# APP_1_FPGA_m.net
KiCad netlist of a schematic drawn in Altium Designer
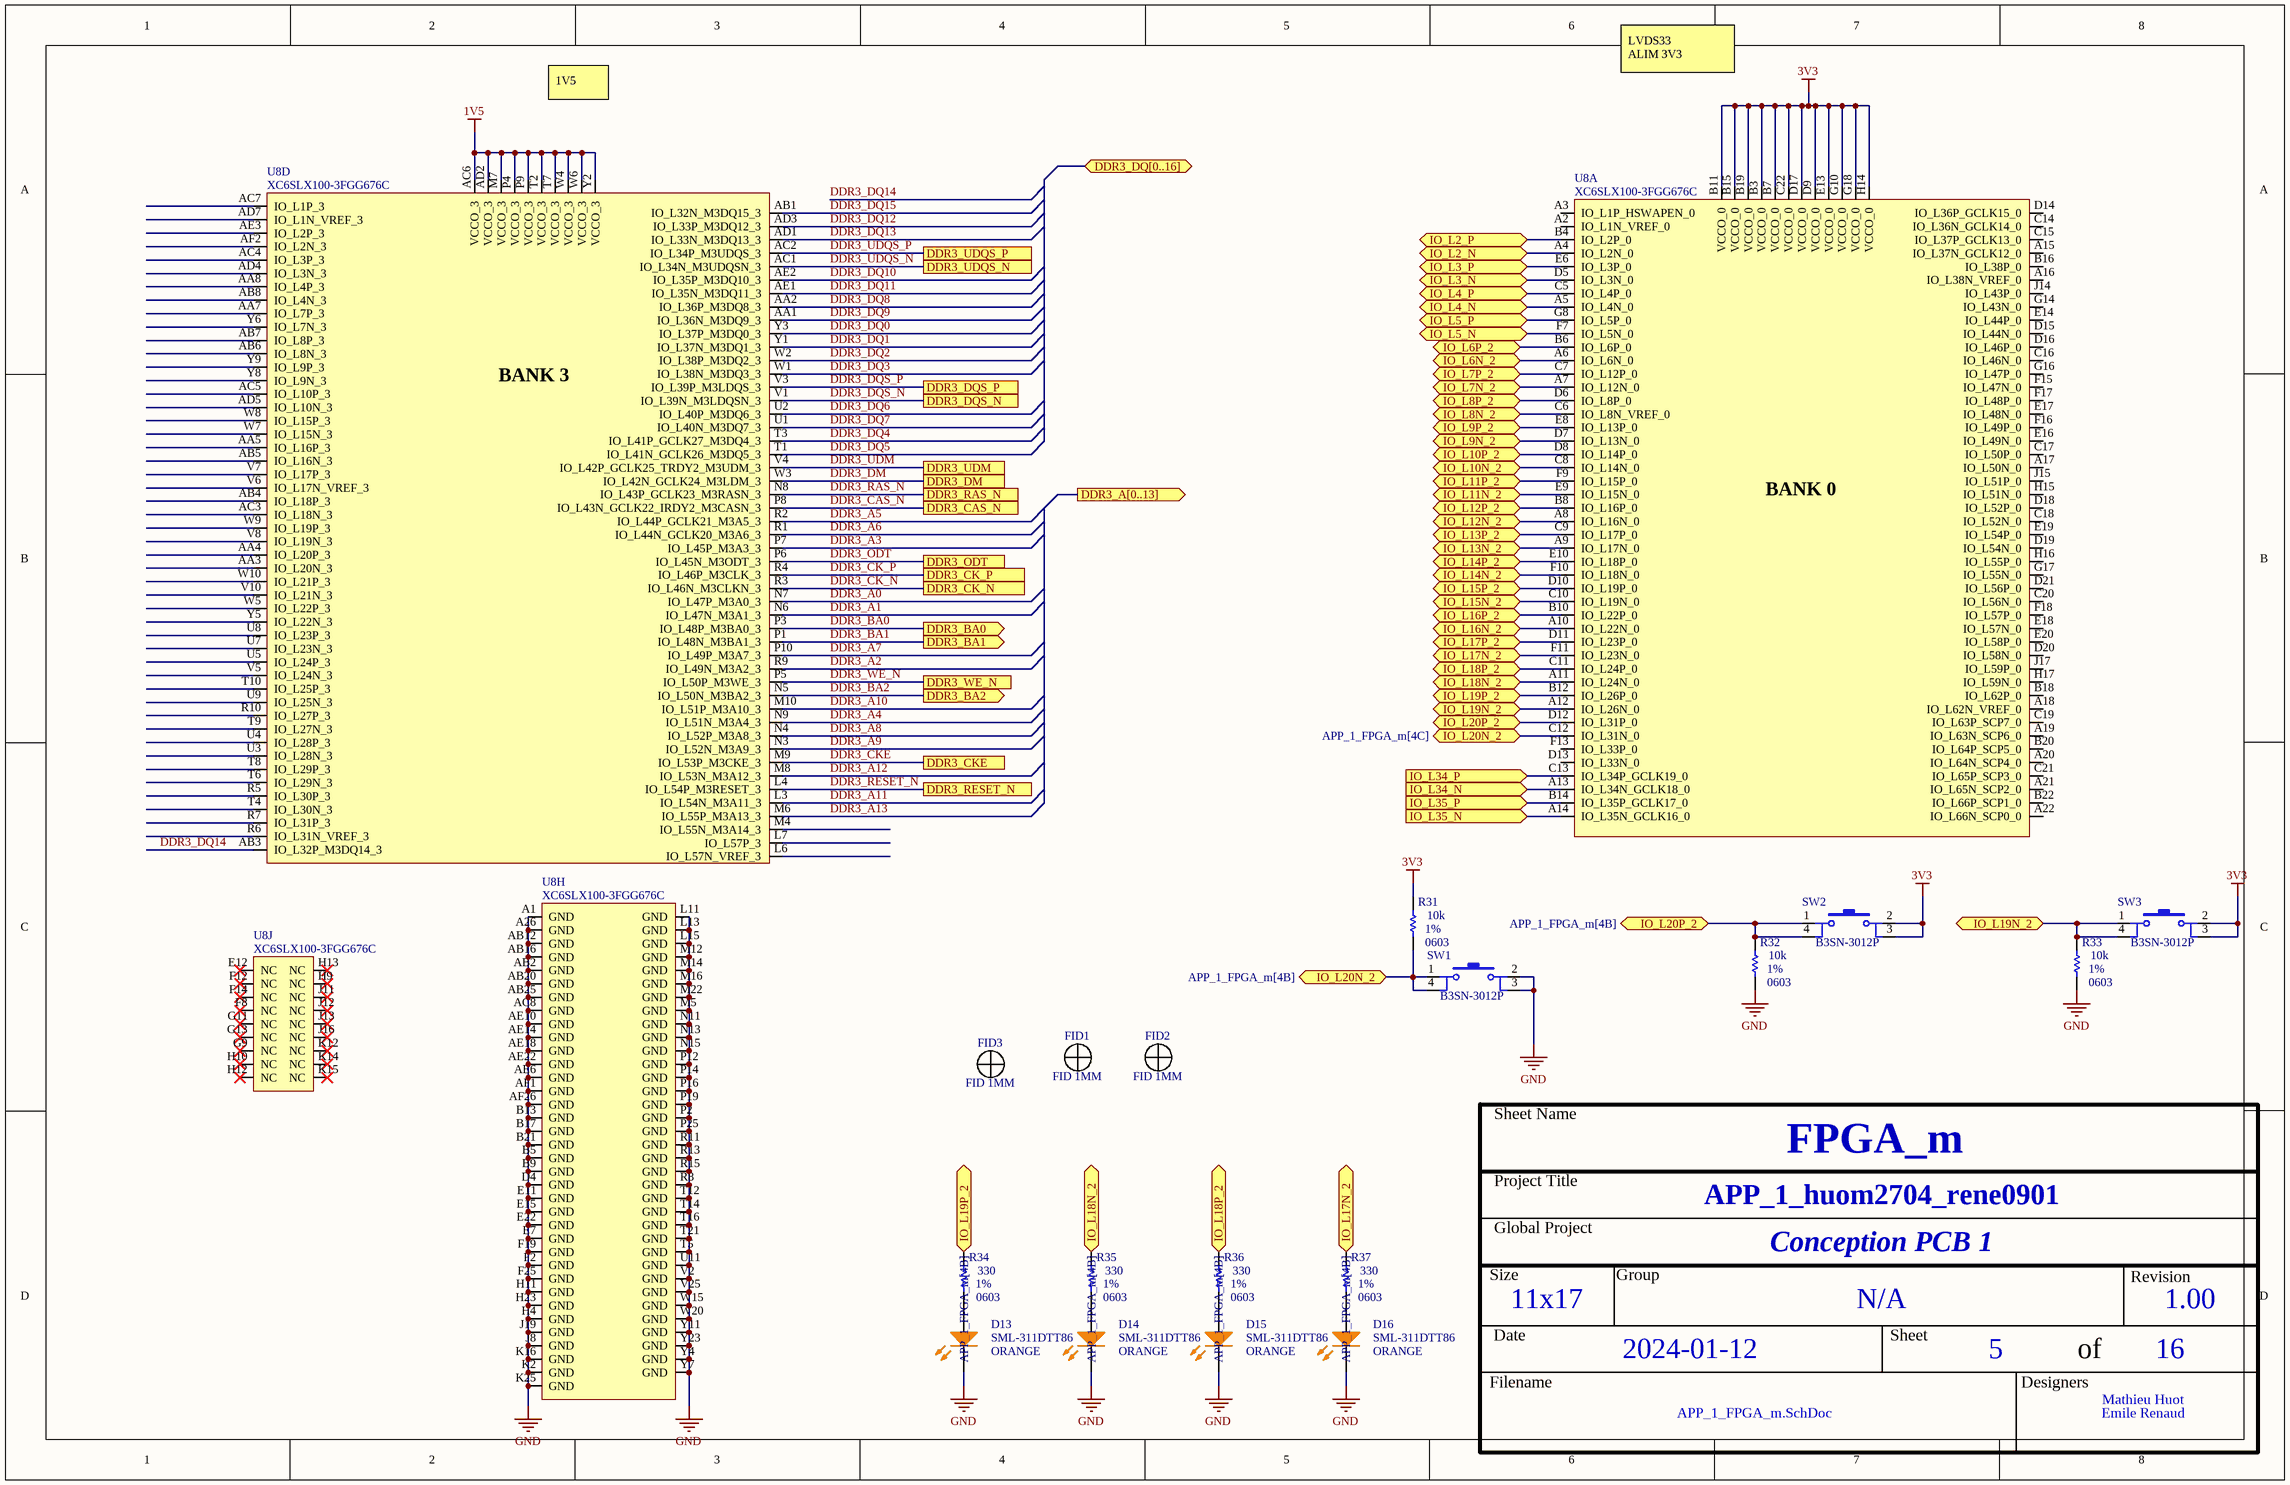
[diagram p0: APP_1_FPGA_m.SchDoc]

(export (version "E")
  (design (tool "Eeschema 10.0.6"))
  (components
    (comp (ref "D13")
      (value "SML-311DTT86")
      (footprint "LED_0603")
      (description "LED - 611nM ORANGE 2mA - 0603")
      (fields
        (field (name "VOLTAGE") "1.8V")
        (field (name "MFG") "ROHM Semiconductor")
        (field (name "ALTIUM_VALUE") "ORANGE")
        (field (name "CREATEDBY") "Jonathan Bouchard")
      )
      (libsource (lib "S7CAS_LIB2023") (part "LED_SML-311DTT86"))
    )
    (comp (ref "D14")
      (value "SML-311DTT86")
      (footprint "LED_0603")
      (description "LED - 611nM ORANGE 2mA - 0603")
      (fields
        (field (name "VOLTAGE") "1.8V")
        (field (name "MFG") "ROHM Semiconductor")
        (field (name "ALTIUM_VALUE") "ORANGE")
        (field (name "CREATEDBY") "Jonathan Bouchard")
      )
      (libsource (lib "S7CAS_LIB2023") (part "LED_SML-311DTT86"))
    )
    (comp (ref "D15")
      (value "SML-311DTT86")
      (footprint "LED_0603")
      (description "LED - 611nM ORANGE 2mA - 0603")
      (fields
        (field (name "VOLTAGE") "1.8V")
        (field (name "MFG") "ROHM Semiconductor")
        (field (name "ALTIUM_VALUE") "ORANGE")
        (field (name "CREATEDBY") "Jonathan Bouchard")
      )
      (libsource (lib "S7CAS_LIB2023") (part "LED_SML-311DTT86"))
    )
    (comp (ref "D16")
      (value "SML-311DTT86")
      (footprint "LED_0603")
      (description "LED - 611nM ORANGE 2mA - 0603")
      (fields
        (field (name "VOLTAGE") "1.8V")
        (field (name "MFG") "ROHM Semiconductor")
        (field (name "ALTIUM_VALUE") "ORANGE")
        (field (name "CREATEDBY") "Jonathan Bouchard")
      )
      (libsource (lib "S7CAS_LIB2023") (part "LED_SML-311DTT86"))
    )
    (comp (ref "FID1")
      (value "FID 1MM")
      (footprint "FID_CIRCLE_1MM")
      (description "FID - FIDUCIAL 1MM CIRCLE DOUBLE-SIDED - 1MM")
      (fields
        (field (name "CREATEDBY/DATE") "Jonathan Bouchard 2018-07-23")
        (field (name "VERIFIEDBY") "Caroline Paulin - 25 juillet 2018")
      )
      (libsource (lib "S7CAS_LIB2023") (part "FID_CIRCLE_1MM"))
    )
    (comp (ref "FID2")
      (value "FID 1MM")
      (footprint "FID_CIRCLE_1MM")
      (description "FID - FIDUCIAL 1MM CIRCLE DOUBLE-SIDED - 1MM")
      (fields
        (field (name "CREATEDBY/DATE") "Jonathan Bouchard 2018-07-23")
        (field (name "VERIFIEDBY") "Caroline Paulin - 25 juillet 2018")
      )
      (libsource (lib "S7CAS_LIB2023") (part "FID_CIRCLE_1MM"))
    )
    (comp (ref "FID3")
      (value "FID 1MM")
      (footprint "FID_CIRCLE_1MM")
      (description "FID - FIDUCIAL 1MM CIRCLE DOUBLE-SIDED - 1MM")
      (fields
        (field (name "CREATEDBY/DATE") "Jonathan Bouchard 2018-07-23")
        (field (name "VERIFIEDBY") "Caroline Paulin - 25 juillet 2018")
      )
      (libsource (lib "S7CAS_LIB2023") (part "FID_CIRCLE_1MM"))
    )
    (comp (ref "R31")
      (value "10k")
      (footprint "RES_0603")
      (description "RES - 0603")
      (fields
        (field (name "PACKAGE") "0603")
        (field (name "PRECISION") "1%")
        (field (name "CREATEDBY") "Jonathan Bouchard")
      )
      (libsource (lib "S7CAS_LIB2023") (part "RES - 0603"))
    )
    (comp (ref "R32")
      (value "10k")
      (footprint "RES_0603")
      (description "RES - 0603")
      (fields
        (field (name "PACKAGE") "0603")
        (field (name "PRECISION") "1%")
        (field (name "CREATEDBY") "Jonathan Bouchard")
      )
      (libsource (lib "S7CAS_LIB2023") (part "RES - 0603"))
    )
    (comp (ref "R33")
      (value "10k")
      (footprint "RES_0603")
      (description "RES - 0603")
      (fields
        (field (name "PACKAGE") "0603")
        (field (name "PRECISION") "1%")
        (field (name "CREATEDBY") "Jonathan Bouchard")
      )
      (libsource (lib "S7CAS_LIB2023") (part "RES - 0603"))
    )
    (comp (ref "R34")
      (value "330")
      (footprint "RES_0603")
      (description "RES - 0603")
      (fields
        (field (name "PACKAGE") "0603")
        (field (name "PRECISION") "1%")
        (field (name "CREATEDBY") "Jonathan Bouchard")
      )
      (libsource (lib "S7CAS_LIB2023") (part "RES - 0603"))
    )
    (comp (ref "R35")
      (value "330")
      (footprint "RES_0603")
      (description "RES - 0603")
      (fields
        (field (name "PACKAGE") "0603")
        (field (name "PRECISION") "1%")
        (field (name "CREATEDBY") "Jonathan Bouchard")
      )
      (libsource (lib "S7CAS_LIB2023") (part "RES - 0603"))
    )
    (comp (ref "R36")
      (value "330")
      (footprint "RES_0603")
      (description "RES - 0603")
      (fields
        (field (name "PACKAGE") "0603")
        (field (name "PRECISION") "1%")
        (field (name "CREATEDBY") "Jonathan Bouchard")
      )
      (libsource (lib "S7CAS_LIB2023") (part "RES - 0603"))
    )
    (comp (ref "R37")
      (value "330")
      (footprint "RES_0603")
      (description "RES - 0603")
      (fields
        (field (name "PACKAGE") "0603")
        (field (name "PRECISION") "1%")
        (field (name "CREATEDBY") "Jonathan Bouchard")
      )
      (libsource (lib "S7CAS_LIB2023") (part "RES - 0603"))
    )
    (comp (ref "SW1")
      (value "B3SN-3012P")
      (footprint "SWI_TACT_B3SN-3012P")
      (description "SWI - TACT SPST-NO 0.05A 24V - 4-SMD")
      (fields
        (field (name "MFG") "Omron")
        (field (name "VOLTAGE") "24V")
        (field (name "CREATEDBY") "Jonathan Bouchard")
      )
      (libsource (lib "S7CAS_LIB2023") (part "SWI_TACT_B3SN-3012P"))
    )
    (comp (ref "SW2")
      (value "B3SN-3012P")
      (footprint "SWI_TACT_B3SN-3012P")
      (description "SWI - TACT SPST-NO 0.05A 24V - 4-SMD")
      (fields
        (field (name "MFG") "Omron")
        (field (name "VOLTAGE") "24V")
        (field (name "CREATEDBY") "Jonathan Bouchard")
      )
      (libsource (lib "S7CAS_LIB2023") (part "SWI_TACT_B3SN-3012P"))
    )
    (comp (ref "SW3")
      (value "B3SN-3012P")
      (footprint "SWI_TACT_B3SN-3012P")
      (description "SWI - TACT SPST-NO 0.05A 24V - 4-SMD")
      (fields
        (field (name "MFG") "Omron")
        (field (name "VOLTAGE") "24V")
        (field (name "CREATEDBY") "Jonathan Bouchard")
      )
      (libsource (lib "S7CAS_LIB2023") (part "SWI_TACT_B3SN-3012P"))
    )
    (comp (ref "U8")
      (value "XC6SLX100-3FGG676C")
      (footprint "FPGA_XILINX_FGG676")
      (description "FPGA - XILINX SPARTAN 6 480 I/O - BGA-676")
      (fields
        (field (name "VOLTAGE") "1.14 V ~ 1.26 V")
        (field (name "MFG") "Xilinx")
        (field (name "CREATEDBY") "Jonathan Bouchard")
      )
      (libsource (lib "S7CAS_LIB2023") (part "FPGA_XC6SLX100-3FGG676C"))
    )
  )
  (nets
    (net (code "2") (name "/DDR3_A0") (class "Default")
      (node (ref "U8") (pin "N7") (pinfunction "IO_L47P_M3A0_3_N7") (pintype "passive"))
    )
    (net (code "3") (name "/DDR3_A1") (class "Default")
      (node (ref "U8") (pin "N6") (pinfunction "IO_L47N_M3A1_3_N6") (pintype "passive"))
    )
    (net (code "4") (name "/DDR3_A2") (class "Default")
      (node (ref "U8") (pin "R9") (pinfunction "IO_L49N_M3A2_3_R9") (pintype "passive"))
    )
    (net (code "5") (name "/DDR3_A3") (class "Default")
      (node (ref "U8") (pin "P7") (pinfunction "IO_L45P_M3A3_3_P7") (pintype "passive"))
    )
    (net (code "6") (name "/DDR3_A4") (class "Default")
      (node (ref "U8") (pin "N9") (pinfunction "IO_L51N_M3A4_3_N9") (pintype "passive"))
    )
    (net (code "7") (name "/DDR3_A5") (class "Default")
      (node (ref "U8") (pin "R2") (pinfunction "IO_L44P_GCLK21_M3A5_3_R2") (pintype "passive"))
    )
    (net (code "8") (name "/DDR3_A6") (class "Default")
      (node (ref "U8") (pin "R1") (pinfunction "IO_L44N_GCLK20_M3A6_3_R1") (pintype "passive"))
    )
    (net (code "9") (name "/DDR3_A7") (class "Default")
      (node (ref "U8") (pin "P10") (pinfunction "IO_L49P_M3A7_3_P10") (pintype "passive"))
    )
    (net (code "10") (name "/DDR3_A8") (class "Default")
      (node (ref "U8") (pin "N4") (pinfunction "IO_L52P_M3A8_3_N4") (pintype "passive"))
    )
    (net (code "11") (name "/DDR3_A9") (class "Default")
      (node (ref "U8") (pin "N3") (pinfunction "IO_L52N_M3A9_3_N3") (pintype "passive"))
    )
    (net (code "12") (name "/DDR3_A10") (class "Default")
      (node (ref "U8") (pin "M10") (pinfunction "IO_L51P_M3A10_3_M10") (pintype "passive"))
    )
    (net (code "13") (name "/DDR3_A11") (class "Default")
      (node (ref "U8") (pin "L3") (pinfunction "IO_L54N_M3A11_3_L3") (pintype "passive"))
    )
    (net (code "14") (name "/DDR3_A12") (class "Default")
      (node (ref "U8") (pin "M8") (pinfunction "IO_L53N_M3A12_3_M8") (pintype "passive"))
    )
    (net (code "15") (name "/DDR3_A13") (class "Default")
      (node (ref "U8") (pin "M6") (pinfunction "IO_L55P_M3A13_3_M6") (pintype "passive"))
    )
    (net (code "17") (name "/DDR3_BA0") (class "Default")
      (node (ref "U8") (pin "P3") (pinfunction "IO_L48P_M3BA0_3_P3") (pintype "passive"))
    )
    (net (code "18") (name "/DDR3_BA1") (class "Default")
      (node (ref "U8") (pin "P1") (pinfunction "IO_L48N_M3BA1_3_P1") (pintype "passive"))
    )
    (net (code "19") (name "/DDR3_BA2") (class "Default")
      (node (ref "U8") (pin "N5") (pinfunction "IO_L50N_M3BA2_3_N5") (pintype "passive"))
    )
    (net (code "20") (name "/DDR3_CAS_N") (class "Default")
      (node (ref "U8") (pin "P8") (pinfunction "IO_L43N_GCLK22_IRDY2_M3CASN_3_P8") (pintype "passive"))
    )
    (net (code "21") (name "/DDR3_CKE") (class "Default")
      (node (ref "U8") (pin "M9") (pinfunction "IO_L53P_M3CKE_3_M9") (pintype "passive"))
    )
    (net (code "22") (name "/DDR3_CK_N") (class "Default")
      (node (ref "U8") (pin "R3") (pinfunction "IO_L46N_M3CLKN_3_R3") (pintype "passive"))
    )
    (net (code "23") (name "/DDR3_CK_P") (class "Default")
      (node (ref "U8") (pin "R4") (pinfunction "IO_L46P_M3CLK_3_R4") (pintype "passive"))
    )
    (net (code "24") (name "/DDR3_DM") (class "Default")
      (node (ref "U8") (pin "W3") (pinfunction "IO_L42N_GCLK24_M3LDM_3_W3") (pintype "passive"))
    )
    (net (code "25") (name "/DDR3_DQ0") (class "Default")
      (node (ref "U8") (pin "Y3") (pinfunction "IO_L37P_M3DQ0_3_Y3") (pintype "passive"))
    )
    (net (code "26") (name "/DDR3_DQ1") (class "Default")
      (node (ref "U8") (pin "Y1") (pinfunction "IO_L37N_M3DQ1_3_Y1") (pintype "passive"))
    )
    (net (code "27") (name "/DDR3_DQ2") (class "Default")
      (node (ref "U8") (pin "W2") (pinfunction "IO_L38P_M3DQ2_3_W2") (pintype "passive"))
    )
    (net (code "28") (name "/DDR3_DQ3") (class "Default")
      (node (ref "U8") (pin "W1") (pinfunction "IO_L38N_M3DQ3_3_W1") (pintype "passive"))
    )
    (net (code "29") (name "/DDR3_DQ4") (class "Default")
      (node (ref "U8") (pin "T3") (pinfunction "IO_L41P_GCLK27_M3DQ4_3_T3") (pintype "passive"))
    )
    (net (code "30") (name "/DDR3_DQ5") (class "Default")
      (node (ref "U8") (pin "T1") (pinfunction "IO_L41N_GCLK26_M3DQ5_3_T1") (pintype "passive"))
    )
    (net (code "31") (name "/DDR3_DQ6") (class "Default")
      (node (ref "U8") (pin "U2") (pinfunction "IO_L40P_M3DQ6_3_U2") (pintype "passive"))
    )
    (net (code "32") (name "/DDR3_DQ7") (class "Default")
      (node (ref "U8") (pin "U1") (pinfunction "IO_L40N_M3DQ7_3_U1") (pintype "passive"))
    )
    (net (code "33") (name "/DDR3_DQ8") (class "Default")
      (node (ref "U8") (pin "AA2") (pinfunction "IO_L36P_M3DQ8_3_AA2") (pintype "passive"))
    )
    (net (code "34") (name "/DDR3_DQ9") (class "Default")
      (node (ref "U8") (pin "AA1") (pinfunction "IO_L36N_M3DQ9_3_AA1") (pintype "passive"))
    )
    (net (code "35") (name "/DDR3_DQ10") (class "Default")
      (node (ref "U8") (pin "AE2") (pinfunction "IO_L35P_M3DQ10_3_AE2") (pintype "passive"))
    )
    (net (code "36") (name "/DDR3_DQ11") (class "Default")
      (node (ref "U8") (pin "AE1") (pinfunction "IO_L35N_M3DQ11_3_AE1") (pintype "passive"))
    )
    (net (code "37") (name "/DDR3_DQ12") (class "Default")
      (node (ref "U8") (pin "AD3") (pinfunction "IO_L33P_M3DQ12_3_AD3") (pintype "passive"))
    )
    (net (code "38") (name "/DDR3_DQ13") (class "Default")
      (node (ref "U8") (pin "AD1") (pinfunction "IO_L33N_M3DQ13_3_AD1") (pintype "passive"))
    )
    (net (code "39") (name "/DDR3_DQ14") (class "Default")
      (node (ref "U8") (pin "AB3") (pinfunction "IO_L32P_M3DQ14_3_AB3") (pintype "passive"))
    )
    (net (code "40") (name "/DDR3_DQ15") (class "Default")
      (node (ref "U8") (pin "AB1") (pinfunction "IO_L32N_M3DQ15_3_AB1") (pintype "passive"))
    )
    (net (code "41") (name "/DDR3_DQS_N") (class "Default")
      (node (ref "U8") (pin "V1") (pinfunction "IO_L39N_M3LDQSN_3_V1") (pintype "passive"))
    )
    (net (code "42") (name "/DDR3_DQS_P") (class "Default")
      (node (ref "U8") (pin "V3") (pinfunction "IO_L39P_M3LDQS_3_V3") (pintype "passive"))
    )
    (net (code "44") (name "/DDR3_ODT") (class "Default")
      (node (ref "U8") (pin "P6") (pinfunction "IO_L45N_M3ODT_3_P6") (pintype "passive"))
    )
    (net (code "45") (name "/DDR3_RAS_N") (class "Default")
      (node (ref "U8") (pin "N8") (pinfunction "IO_L43P_GCLK23_M3RASN_3_N8") (pintype "passive"))
    )
    (net (code "46") (name "/DDR3_RESET_N") (class "Default")
      (node (ref "U8") (pin "L4") (pinfunction "IO_L54P_M3RESET_3_L4") (pintype "passive"))
    )
    (net (code "47") (name "/DDR3_UDM") (class "Default")
      (node (ref "U8") (pin "V4") (pinfunction "IO_L42P_GCLK25_TRDY2_M3UDM_3_V4") (pintype "passive"))
    )
    (net (code "48") (name "/DDR3_UDQS_N") (class "Default")
      (node (ref "U8") (pin "AC1") (pinfunction "IO_L34N_M3UDQSN_3_AC1") (pintype "passive"))
    )
    (net (code "49") (name "/DDR3_UDQS_P") (class "Default")
      (node (ref "U8") (pin "AC2") (pinfunction "IO_L34P_M3UDQS_3_AC2") (pintype "passive"))
    )
    (net (code "50") (name "/DDR3_WE_N") (class "Default")
      (node (ref "U8") (pin "P5") (pinfunction "IO_L50P_M3WE_3_P5") (pintype "passive"))
    )
    (net (code "51") (name "/IO_L2_N") (class "Default")
      (node (ref "U8") (pin "A4") (pinfunction "IO_L2N_0_A4") (pintype "passive"))
    )
    (net (code "52") (name "/IO_L2_P") (class "Default")
      (node (ref "U8") (pin "B4") (pinfunction "IO_L2P_0_B4") (pintype "passive"))
    )
    (net (code "53") (name "/IO_L3_N") (class "Default")
      (node (ref "U8") (pin "D5") (pinfunction "IO_L3N_0_D5") (pintype "passive"))
    )
    (net (code "54") (name "/IO_L3_P") (class "Default")
      (node (ref "U8") (pin "E6") (pinfunction "IO_L3P_0_E6") (pintype "passive"))
    )
    (net (code "55") (name "/IO_L4_N") (class "Default")
      (node (ref "U8") (pin "A5") (pinfunction "IO_L4N_0_A5") (pintype "passive"))
    )
    (net (code "56") (name "/IO_L4_P") (class "Default")
      (node (ref "U8") (pin "C5") (pinfunction "IO_L4P_0_C5") (pintype "passive"))
    )
    (net (code "57") (name "/IO_L5_N") (class "Default")
      (node (ref "U8") (pin "F7") (pinfunction "IO_L5N_0_F7") (pintype "passive"))
    )
    (net (code "58") (name "/IO_L5_P") (class "Default")
      (node (ref "U8") (pin "G8") (pinfunction "IO_L5P_0_G8") (pintype "passive"))
    )
    (net (code "59") (name "/IO_L6N_2") (class "Default")
      (node (ref "U8") (pin "A6") (pinfunction "IO_L6N_0_A6") (pintype "passive"))
    )
    (net (code "60") (name "/IO_L6P_2") (class "Default")
      (node (ref "U8") (pin "B6") (pinfunction "IO_L6P_0_B6") (pintype "passive"))
    )
    (net (code "61") (name "/IO_L7N_2") (class "Default")
      (node (ref "U8") (pin "A7") (pinfunction "IO_L12N_0_A7") (pintype "passive"))
    )
    (net (code "62") (name "/IO_L7P_2") (class "Default")
      (node (ref "U8") (pin "C7") (pinfunction "IO_L12P_0_C7") (pintype "passive"))
    )
    (net (code "63") (name "/IO_L8N_2") (class "Default")
      (node (ref "U8") (pin "C6") (pinfunction "IO_L8N_VREF_0_C6") (pintype "passive"))
    )
    (net (code "64") (name "/IO_L8P_2") (class "Default")
      (node (ref "U8") (pin "D6") (pinfunction "IO_L8P_0_D6") (pintype "passive"))
    )
    (net (code "65") (name "/IO_L9N_2") (class "Default")
      (node (ref "U8") (pin "D7") (pinfunction "IO_L13N_0_D7") (pintype "passive"))
    )
    (net (code "66") (name "/IO_L9P_2") (class "Default")
      (node (ref "U8") (pin "E8") (pinfunction "IO_L13P_0_E8") (pintype "passive"))
    )
    (net (code "67") (name "/IO_L10N_2") (class "Default")
      (node (ref "U8") (pin "C8") (pinfunction "IO_L14N_0_C8") (pintype "passive"))
    )
    (net (code "68") (name "/IO_L10P_2") (class "Default")
      (node (ref "U8") (pin "D8") (pinfunction "IO_L14P_0_D8") (pintype "passive"))
    )
    (net (code "69") (name "/IO_L11N_2") (class "Default")
      (node (ref "U8") (pin "E9") (pinfunction "IO_L15N_0_E9") (pintype "passive"))
    )
    (net (code "70") (name "/IO_L11P_2") (class "Default")
      (node (ref "U8") (pin "F9") (pinfunction "IO_L15P_0_F9") (pintype "passive"))
    )
    (net (code "71") (name "/IO_L12N_2") (class "Default")
      (node (ref "U8") (pin "A8") (pinfunction "IO_L16N_0_A8") (pintype "passive"))
    )
    (net (code "72") (name "/IO_L12P_2") (class "Default")
      (node (ref "U8") (pin "B8") (pinfunction "IO_L16P_0_B8") (pintype "passive"))
    )
    (net (code "73") (name "/IO_L13N_2") (class "Default")
      (node (ref "U8") (pin "A9") (pinfunction "IO_L17N_0_A9") (pintype "passive"))
    )
    (net (code "74") (name "/IO_L13P_2") (class "Default")
      (node (ref "U8") (pin "C9") (pinfunction "IO_L17P_0_C9") (pintype "passive"))
    )
    (net (code "75") (name "/IO_L14N_2") (class "Default")
      (node (ref "U8") (pin "F10") (pinfunction "IO_L18N_0_F10") (pintype "passive"))
    )
    (net (code "76") (name "/IO_L14P_2") (class "Default")
      (node (ref "U8") (pin "E10") (pinfunction "IO_L18P_0_E10") (pintype "passive"))
    )
    (net (code "77") (name "/IO_L15N_2") (class "Default")
      (node (ref "U8") (pin "C10") (pinfunction "IO_L19N_0_C10") (pintype "passive"))
    )
    (net (code "78") (name "/IO_L15P_2") (class "Default")
      (node (ref "U8") (pin "D10") (pinfunction "IO_L19P_0_D10") (pintype "passive"))
    )
    (net (code "79") (name "/IO_L16N_2") (class "Default")
      (node (ref "U8") (pin "A10") (pinfunction "IO_L22N_0_A10") (pintype "passive"))
    )
    (net (code "80") (name "/IO_L16P_2") (class "Default")
      (node (ref "U8") (pin "B10") (pinfunction "IO_L22P_0_B10") (pintype "passive"))
    )
    (net (code "81") (name "/IO_L17N_2") (class "Default")
      (node (ref "R37") (pin "2") (pinfunction "2_2") (pintype "passive"))
      (node (ref "U8") (pin "F11") (pinfunction "IO_L23N_0_F11") (pintype "passive"))
    )
    (net (code "82") (name "/IO_L17P_2") (class "Default")
      (node (ref "U8") (pin "D11") (pinfunction "IO_L23P_0_D11") (pintype "passive"))
    )
    (net (code "83") (name "/IO_L18N_2") (class "Default")
      (node (ref "R35") (pin "2") (pinfunction "2_2") (pintype "passive"))
      (node (ref "U8") (pin "A11") (pinfunction "IO_L24N_0_A11") (pintype "passive"))
    )
    (net (code "84") (name "/IO_L18P_2") (class "Default")
      (node (ref "R36") (pin "2") (pinfunction "2_2") (pintype "passive"))
      (node (ref "U8") (pin "C11") (pinfunction "IO_L24P_0_C11") (pintype "passive"))
    )
    (net (code "85") (name "/IO_L19N_2") (class "Default")
      (node (ref "R33") (pin "2") (pinfunction "2_2") (pintype "passive"))
      (node (ref "SW3") (pin "1") (pinfunction "1_1") (pintype "passive"))
      (node (ref "SW3") (pin "4") (pinfunction "4_4") (pintype "passive"))
      (node (ref "U8") (pin "A12") (pinfunction "IO_L26N_0_A12") (pintype "passive"))
    )
    (net (code "86") (name "/IO_L19P_2") (class "Default")
      (node (ref "R34") (pin "2") (pinfunction "2_2") (pintype "passive"))
      (node (ref "U8") (pin "B12") (pinfunction "IO_L26P_0_B12") (pintype "passive"))
    )
    (net (code "87") (name "/IO_L20N_2") (class "Default")
      (node (ref "R31") (pin "1") (pinfunction "1_1") (pintype "passive"))
      (node (ref "SW1") (pin "1") (pinfunction "1_1") (pintype "passive"))
      (node (ref "SW1") (pin "4") (pinfunction "4_4") (pintype "passive"))
      (node (ref "U8") (pin "C12") (pinfunction "IO_L31N_0_C12") (pintype "passive"))
    )
    (net (code "88") (name "/IO_L20P_2") (class "Default")
      (node (ref "R32") (pin "2") (pinfunction "2_2") (pintype "passive"))
      (node (ref "SW2") (pin "1") (pinfunction "1_1") (pintype "passive"))
      (node (ref "SW2") (pin "4") (pinfunction "4_4") (pintype "passive"))
      (node (ref "U8") (pin "D12") (pinfunction "IO_L31P_0_D12") (pintype "passive"))
    )
    (net (code "89") (name "/IO_L34_N") (class "Default")
      (node (ref "U8") (pin "A13") (pinfunction "IO_L34N_GCLK18_0_A13") (pintype "passive"))
    )
    (net (code "90") (name "/IO_L34_P") (class "Default")
      (node (ref "U8") (pin "C13") (pinfunction "IO_L34P_GCLK19_0_C13") (pintype "passive"))
    )
    (net (code "91") (name "/IO_L35_N") (class "Default")
      (node (ref "U8") (pin "A14") (pinfunction "IO_L35N_GCLK16_0_A14") (pintype "passive"))
    )
    (net (code "92") (name "/IO_L35_P") (class "Default")
      (node (ref "U8") (pin "B14") (pinfunction "IO_L35P_GCLK17_0_B14") (pintype "passive"))
    )
    (net (code "93") (name "1V5") (class "Default")
      (node (ref "U8") (pin "AC6") (pinfunction "VCCO_3_AC6") (pintype "passive"))
      (node (ref "U8") (pin "AD2") (pinfunction "VCCO_3_AD2") (pintype "passive"))
      (node (ref "U8") (pin "M7") (pinfunction "VCCO_3_M7") (pintype "passive"))
      (node (ref "U8") (pin "P4") (pinfunction "VCCO_3_P4") (pintype "passive"))
      (node (ref "U8") (pin "P9") (pinfunction "VCCO_3_P9") (pintype "passive"))
      (node (ref "U8") (pin "T2") (pinfunction "VCCO_3_T2") (pintype "passive"))
      (node (ref "U8") (pin "T7") (pinfunction "VCCO_3_T7") (pintype "passive"))
      (node (ref "U8") (pin "W4") (pinfunction "VCCO_3_W4") (pintype "passive"))
      (node (ref "U8") (pin "W6") (pinfunction "VCCO_3_W6") (pintype "passive"))
      (node (ref "U8") (pin "Y2") (pinfunction "VCCO_3_Y2") (pintype "passive"))
    )
    (net (code "94") (name "3V3") (class "Default")
      (node (ref "R31") (pin "2") (pinfunction "2_2") (pintype "passive"))
      (node (ref "SW2") (pin "2") (pinfunction "2_2") (pintype "passive"))
      (node (ref "SW2") (pin "3") (pinfunction "3_3") (pintype "passive"))
      (node (ref "SW3") (pin "2") (pinfunction "2_2") (pintype "passive"))
      (node (ref "SW3") (pin "3") (pinfunction "3_3") (pintype "passive"))
      (node (ref "U8") (pin "B11") (pinfunction "VCCO_0_B11") (pintype "passive"))
      (node (ref "U8") (pin "B15") (pinfunction "VCCO_0_B15") (pintype "passive"))
      (node (ref "U8") (pin "B19") (pinfunction "VCCO_0_B19") (pintype "passive"))
      (node (ref "U8") (pin "B3") (pinfunction "VCCO_0_B3") (pintype "passive"))
      (node (ref "U8") (pin "B7") (pinfunction "VCCO_0_B7") (pintype "passive"))
      (node (ref "U8") (pin "C22") (pinfunction "VCCO_0_C22") (pintype "passive"))
      (node (ref "U8") (pin "D17") (pinfunction "VCCO_0_D17") (pintype "passive"))
      (node (ref "U8") (pin "D9") (pinfunction "VCCO_0_D9") (pintype "passive"))
      (node (ref "U8") (pin "E13") (pinfunction "VCCO_0_E13") (pintype "passive"))
      (node (ref "U8") (pin "G10") (pinfunction "VCCO_0_G10") (pintype "passive"))
      (node (ref "U8") (pin "G18") (pinfunction "VCCO_0_G18") (pintype "passive"))
      (node (ref "U8") (pin "H14") (pinfunction "VCCO_0_H14") (pintype "passive"))
    )
    (net (code "95") (name "GND") (class "Default")
      (node (ref "D13") (pin "K") (pinfunction "K_K") (pintype "passive"))
      (node (ref "D14") (pin "K") (pinfunction "K_K") (pintype "passive"))
      (node (ref "D15") (pin "K") (pinfunction "K_K") (pintype "passive"))
      (node (ref "D16") (pin "K") (pinfunction "K_K") (pintype "passive"))
      (node (ref "R32") (pin "1") (pinfunction "1_1") (pintype "passive"))
      (node (ref "R33") (pin "1") (pinfunction "1_1") (pintype "passive"))
      (node (ref "SW1") (pin "2") (pinfunction "2_2") (pintype "passive"))
      (node (ref "SW1") (pin "3") (pinfunction "3_3") (pintype "passive"))
      (node (ref "U8") (pin "A1") (pinfunction "GND_A1") (pintype "passive"))
      (node (ref "U8") (pin "A26") (pinfunction "GND_A26") (pintype "passive"))
      (node (ref "U8") (pin "AB12") (pinfunction "GND_AB12") (pintype "passive"))
      (node (ref "U8") (pin "AB16") (pinfunction "GND_AB16") (pintype "passive"))
      (node (ref "U8") (pin "AB2") (pinfunction "GND_AB2") (pintype "passive"))
      (node (ref "U8") (pin "AB20") (pinfunction "GND_AB20") (pintype "passive"))
      (node (ref "U8") (pin "AB25") (pinfunction "GND_AB25") (pintype "passive"))
      (node (ref "U8") (pin "AC8") (pinfunction "GND_AC8") (pintype "passive"))
      (node (ref "U8") (pin "AE10") (pinfunction "GND_AE10") (pintype "passive"))
      (node (ref "U8") (pin "AE14") (pinfunction "GND_AE14") (pintype "passive"))
      (node (ref "U8") (pin "AE18") (pinfunction "GND_AE18") (pintype "passive"))
      (node (ref "U8") (pin "AE22") (pinfunction "GND_AE22") (pintype "passive"))
      (node (ref "U8") (pin "AE6") (pinfunction "GND_AE6") (pintype "passive"))
      (node (ref "U8") (pin "AF1") (pinfunction "GND_AF1") (pintype "passive"))
      (node (ref "U8") (pin "AF26") (pinfunction "GND_AF26") (pintype "passive"))
      (node (ref "U8") (pin "B13") (pinfunction "GND_B13") (pintype "passive"))
      (node (ref "U8") (pin "B17") (pinfunction "GND_B17") (pintype "passive"))
      (node (ref "U8") (pin "B21") (pinfunction "GND_B21") (pintype "passive"))
      (node (ref "U8") (pin "B5") (pinfunction "GND_B5") (pintype "passive"))
      (node (ref "U8") (pin "B9") (pinfunction "GND_B9") (pintype "passive"))
      (node (ref "U8") (pin "D4") (pinfunction "GND_D4") (pintype "passive"))
      (node (ref "U8") (pin "E11") (pinfunction "GND_E11") (pintype "passive"))
      (node (ref "U8") (pin "E15") (pinfunction "GND_E15") (pintype "passive"))
      (node (ref "U8") (pin "E22") (pinfunction "GND_E22") (pintype "passive"))
      (node (ref "U8") (pin "E7") (pinfunction "GND_E7") (pintype "passive"))
      (node (ref "U8") (pin "F19") (pinfunction "GND_F19") (pintype "passive"))
      (node (ref "U8") (pin "F2") (pinfunction "GND_F2") (pintype "passive"))
      (node (ref "U8") (pin "F25") (pinfunction "GND_F25") (pintype "passive"))
      (node (ref "U8") (pin "H11") (pinfunction "GND_H11") (pintype "passive"))
      (node (ref "U8") (pin "H23") (pinfunction "GND_H23") (pintype "passive"))
      (node (ref "U8") (pin "H4") (pinfunction "GND_H4") (pintype "passive"))
      (node (ref "U8") (pin "J19") (pinfunction "GND_J19") (pintype "passive"))
      (node (ref "U8") (pin "J8") (pinfunction "GND_J8") (pintype "passive"))
      (node (ref "U8") (pin "K16") (pinfunction "GND_K16") (pintype "passive"))
      (node (ref "U8") (pin "K2") (pinfunction "GND_K2") (pintype "passive"))
      (node (ref "U8") (pin "K25") (pinfunction "GND_K25") (pintype "passive"))
      (node (ref "U8") (pin "L11") (pinfunction "GND_L11") (pintype "passive"))
      (node (ref "U8") (pin "L13") (pinfunction "GND_L13") (pintype "passive"))
      (node (ref "U8") (pin "L15") (pinfunction "GND_L15") (pintype "passive"))
      (node (ref "U8") (pin "M12") (pinfunction "GND_M12") (pintype "passive"))
      (node (ref "U8") (pin "M14") (pinfunction "GND_M14") (pintype "passive"))
      (node (ref "U8") (pin "M16") (pinfunction "GND_M16") (pintype "passive"))
      (node (ref "U8") (pin "M22") (pinfunction "GND_M22") (pintype "passive"))
      (node (ref "U8") (pin "M5") (pinfunction "GND_M5") (pintype "passive"))
      (node (ref "U8") (pin "N11") (pinfunction "GND_N11") (pintype "passive"))
      (node (ref "U8") (pin "N13") (pinfunction "GND_N13") (pintype "passive"))
      (node (ref "U8") (pin "N15") (pinfunction "GND_N15") (pintype "passive"))
      (node (ref "U8") (pin "P12") (pinfunction "GND_P12") (pintype "passive"))
      (node (ref "U8") (pin "P14") (pinfunction "GND_P14") (pintype "passive"))
      (node (ref "U8") (pin "P16") (pinfunction "GND_P16") (pintype "passive"))
      (node (ref "U8") (pin "P19") (pinfunction "GND_P19") (pintype "passive"))
      (node (ref "U8") (pin "P2") (pinfunction "GND_P2") (pintype "passive"))
      (node (ref "U8") (pin "P25") (pinfunction "GND_P25") (pintype "passive"))
      (node (ref "U8") (pin "R11") (pinfunction "GND_R11") (pintype "passive"))
      (node (ref "U8") (pin "R13") (pinfunction "GND_R13") (pintype "passive"))
      (node (ref "U8") (pin "R15") (pinfunction "GND_R15") (pintype "passive"))
      (node (ref "U8") (pin "R8") (pinfunction "GND_R8") (pintype "passive"))
      (node (ref "U8") (pin "T12") (pinfunction "GND_T12") (pintype "passive"))
      (node (ref "U8") (pin "T14") (pinfunction "GND_T14") (pintype "passive"))
      (node (ref "U8") (pin "T16") (pinfunction "GND_T16") (pintype "passive"))
      (node (ref "U8") (pin "T21") (pinfunction "GND_T21") (pintype "passive"))
      (node (ref "U8") (pin "T5") (pinfunction "GND_T5") (pintype "passive"))
      (node (ref "U8") (pin "U11") (pinfunction "GND_U11") (pintype "passive"))
      (node (ref "U8") (pin "V2") (pinfunction "GND_V2") (pintype "passive"))
      (node (ref "U8") (pin "V25") (pinfunction "GND_V25") (pintype "passive"))
      (node (ref "U8") (pin "W15") (pinfunction "GND_W15") (pintype "passive"))
      (node (ref "U8") (pin "W20") (pinfunction "GND_W20") (pintype "passive"))
      (node (ref "U8") (pin "Y11") (pinfunction "GND_Y11") (pintype "passive"))
      (node (ref "U8") (pin "Y23") (pinfunction "GND_Y23") (pintype "passive"))
      (node (ref "U8") (pin "Y4") (pinfunction "GND_Y4") (pintype "passive"))
      (node (ref "U8") (pin "Y7") (pinfunction "GND_Y7") (pintype "passive"))
    )
    (net (code "96") (name "Net-(D13-PadA)") (class "Default")
      (node (ref "D13") (pin "A") (pinfunction "A_A") (pintype "passive"))
      (node (ref "R34") (pin "1") (pinfunction "1_1") (pintype "passive"))
    )
    (net (code "97") (name "Net-(D14-PadA)") (class "Default")
      (node (ref "D14") (pin "A") (pinfunction "A_A") (pintype "passive"))
      (node (ref "R35") (pin "1") (pinfunction "1_1") (pintype "passive"))
    )
    (net (code "98") (name "Net-(D15-PadA)") (class "Default")
      (node (ref "D15") (pin "A") (pinfunction "A_A") (pintype "passive"))
      (node (ref "R36") (pin "1") (pinfunction "1_1") (pintype "passive"))
    )
    (net (code "99") (name "Net-(D16-PadA)") (class "Default")
      (node (ref "D16") (pin "A") (pinfunction "A_A") (pintype "passive"))
      (node (ref "R37") (pin "1") (pinfunction "1_1") (pintype "passive"))
    )
    (net (code "100") (name "unconnected-(FID1-Pad1)") (class "Default")
      (node (ref "FID1") (pin "1") (pinfunction "1_1") (pintype "passive"))
    )
    (net (code "101") (name "unconnected-(FID1-Pad2)") (class "Default")
      (node (ref "FID1") (pin "2") (pinfunction "2_2") (pintype "passive"))
    )
    (net (code "102") (name "unconnected-(FID2-Pad1)") (class "Default")
      (node (ref "FID2") (pin "1") (pinfunction "1_1") (pintype "passive"))
    )
    (net (code "103") (name "unconnected-(FID2-Pad2)") (class "Default")
      (node (ref "FID2") (pin "2") (pinfunction "2_2") (pintype "passive"))
    )
    (net (code "104") (name "unconnected-(FID3-Pad1)") (class "Default")
      (node (ref "FID3") (pin "1") (pinfunction "1_1") (pintype "passive"))
    )
    (net (code "105") (name "unconnected-(FID3-Pad2)") (class "Default")
      (node (ref "FID3") (pin "2") (pinfunction "2_2") (pintype "passive"))
    )
    (net (code "106") (name "unconnected-(U8A-IO_L1N_VREF_0-PadA2)") (class "Default")
      (node (ref "U8") (pin "A2") (pinfunction "IO_L1N_VREF_0_A2") (pintype "passive"))
    )
    (net (code "107") (name "unconnected-(U8A-IO_L1P_HSWAPEN_0-PadA3)") (class "Default")
      (node (ref "U8") (pin "A3") (pinfunction "IO_L1P_HSWAPEN_0_A3") (pintype "passive"))
    )
    (net (code "108") (name "unconnected-(U8A-IO_L33N_0-PadD13)") (class "Default")
      (node (ref "U8") (pin "D13") (pinfunction "IO_L33N_0_D13") (pintype "passive"))
    )
    (net (code "109") (name "unconnected-(U8A-IO_L33P_0-PadF13)") (class "Default")
      (node (ref "U8") (pin "F13") (pinfunction "IO_L33P_0_F13") (pintype "passive"))
    )
    (net (code "110") (name "unconnected-(U8A-IO_L36N_GCLK14_0-PadC14)") (class "Default")
      (node (ref "U8") (pin "C14") (pinfunction "IO_L36N_GCLK14_0_C14") (pintype "passive"))
    )
    (net (code "111") (name "unconnected-(U8A-IO_L36P_GCLK15_0-PadD14)") (class "Default")
      (node (ref "U8") (pin "D14") (pinfunction "IO_L36P_GCLK15_0_D14") (pintype "passive"))
    )
    (net (code "112") (name "unconnected-(U8A-IO_L37N_GCLK12_0-PadA15)") (class "Default")
      (node (ref "U8") (pin "A15") (pinfunction "IO_L37N_GCLK12_0_A15") (pintype "passive"))
    )
    (net (code "113") (name "unconnected-(U8A-IO_L37P_GCLK13_0-PadC15)") (class "Default")
      (node (ref "U8") (pin "C15") (pinfunction "IO_L37P_GCLK13_0_C15") (pintype "passive"))
    )
    (net (code "114") (name "unconnected-(U8A-IO_L38N_VREF_0-PadA16)") (class "Default")
      (node (ref "U8") (pin "A16") (pinfunction "IO_L38N_VREF_0_A16") (pintype "passive"))
    )
    (net (code "115") (name "unconnected-(U8A-IO_L38P_0-PadB16)") (class "Default")
      (node (ref "U8") (pin "B16") (pinfunction "IO_L38P_0_B16") (pintype "passive"))
    )
    (net (code "116") (name "unconnected-(U8A-IO_L43N_0-PadG14)") (class "Default")
      (node (ref "U8") (pin "G14") (pinfunction "IO_L43N_0_G14") (pintype "passive"))
    )
    (net (code "117") (name "unconnected-(U8A-IO_L43P_0-PadJ14)") (class "Default")
      (node (ref "U8") (pin "J14") (pinfunction "IO_L43P_0_J14") (pintype "passive"))
    )
    (net (code "118") (name "unconnected-(U8A-IO_L44N_0-PadD15)") (class "Default")
      (node (ref "U8") (pin "D15") (pinfunction "IO_L44N_0_D15") (pintype "passive"))
    )
    (net (code "119") (name "unconnected-(U8A-IO_L44P_0-PadE14)") (class "Default")
      (node (ref "U8") (pin "E14") (pinfunction "IO_L44P_0_E14") (pintype "passive"))
    )
    (net (code "120") (name "unconnected-(U8A-IO_L46N_0-PadC16)") (class "Default")
      (node (ref "U8") (pin "C16") (pinfunction "IO_L46N_0_C16") (pintype "passive"))
    )
    (net (code "121") (name "unconnected-(U8A-IO_L46P_0-PadD16)") (class "Default")
      (node (ref "U8") (pin "D16") (pinfunction "IO_L46P_0_D16") (pintype "passive"))
    )
    (net (code "122") (name "unconnected-(U8A-IO_L47N_0-PadF15)") (class "Default")
      (node (ref "U8") (pin "F15") (pinfunction "IO_L47N_0_F15") (pintype "passive"))
    )
    (net (code "123") (name "unconnected-(U8A-IO_L47P_0-PadG16)") (class "Default")
      (node (ref "U8") (pin "G16") (pinfunction "IO_L47P_0_G16") (pintype "passive"))
    )
    (net (code "124") (name "unconnected-(U8A-IO_L48N_0-PadE17)") (class "Default")
      (node (ref "U8") (pin "E17") (pinfunction "IO_L48N_0_E17") (pintype "passive"))
    )
    (net (code "125") (name "unconnected-(U8A-IO_L48P_0-PadF17)") (class "Default")
      (node (ref "U8") (pin "F17") (pinfunction "IO_L48P_0_F17") (pintype "passive"))
    )
    (net (code "126") (name "unconnected-(U8A-IO_L49N_0-PadE16)") (class "Default")
      (node (ref "U8") (pin "E16") (pinfunction "IO_L49N_0_E16") (pintype "passive"))
    )
    (net (code "127") (name "unconnected-(U8A-IO_L49P_0-PadF16)") (class "Default")
      (node (ref "U8") (pin "F16") (pinfunction "IO_L49P_0_F16") (pintype "passive"))
    )
    (net (code "128") (name "unconnected-(U8A-IO_L50N_0-PadA17)") (class "Default")
      (node (ref "U8") (pin "A17") (pinfunction "IO_L50N_0_A17") (pintype "passive"))
    )
    (net (code "129") (name "unconnected-(U8A-IO_L50P_0-PadC17)") (class "Default")
      (node (ref "U8") (pin "C17") (pinfunction "IO_L50P_0_C17") (pintype "passive"))
    )
    (net (code "130") (name "unconnected-(U8A-IO_L51N_0-PadH15)") (class "Default")
      (node (ref "U8") (pin "H15") (pinfunction "IO_L51N_0_H15") (pintype "passive"))
    )
    (net (code "131") (name "unconnected-(U8A-IO_L51P_0-PadJ15)") (class "Default")
      (node (ref "U8") (pin "J15") (pinfunction "IO_L51P_0_J15") (pintype "passive"))
    )
    (net (code "132") (name "unconnected-(U8A-IO_L52N_0-PadC18)") (class "Default")
      (node (ref "U8") (pin "C18") (pinfunction "IO_L52N_0_C18") (pintype "passive"))
    )
    (net (code "133") (name "unconnected-(U8A-IO_L52P_0-PadD18)") (class "Default")
      (node (ref "U8") (pin "D18") (pinfunction "IO_L52P_0_D18") (pintype "passive"))
    )
    (net (code "134") (name "unconnected-(U8A-IO_L54N_0-PadD19)") (class "Default")
      (node (ref "U8") (pin "D19") (pinfunction "IO_L54N_0_D19") (pintype "passive"))
    )
    (net (code "135") (name "unconnected-(U8A-IO_L54P_0-PadE19)") (class "Default")
      (node (ref "U8") (pin "E19") (pinfunction "IO_L54P_0_E19") (pintype "passive"))
    )
    (net (code "136") (name "unconnected-(U8A-IO_L55N_0-PadG17)") (class "Default")
      (node (ref "U8") (pin "G17") (pinfunction "IO_L55N_0_G17") (pintype "passive"))
    )
    (net (code "137") (name "unconnected-(U8A-IO_L55P_0-PadH16)") (class "Default")
      (node (ref "U8") (pin "H16") (pinfunction "IO_L55P_0_H16") (pintype "passive"))
    )
    (net (code "138") (name "unconnected-(U8A-IO_L56N_0-PadC20)") (class "Default")
      (node (ref "U8") (pin "C20") (pinfunction "IO_L56N_0_C20") (pintype "passive"))
    )
    (net (code "139") (name "unconnected-(U8A-IO_L56P_0-PadD21)") (class "Default")
      (node (ref "U8") (pin "D21") (pinfunction "IO_L56P_0_D21") (pintype "passive"))
    )
    (net (code "140") (name "unconnected-(U8A-IO_L57N_0-PadE18)") (class "Default")
      (node (ref "U8") (pin "E18") (pinfunction "IO_L57N_0_E18") (pintype "passive"))
    )
    (net (code "141") (name "unconnected-(U8A-IO_L57P_0-PadF18)") (class "Default")
      (node (ref "U8") (pin "F18") (pinfunction "IO_L57P_0_F18") (pintype "passive"))
    )
    (net (code "142") (name "unconnected-(U8A-IO_L58N_0-PadD20)") (class "Default")
      (node (ref "U8") (pin "D20") (pinfunction "IO_L58N_0_D20") (pintype "passive"))
    )
    (net (code "143") (name "unconnected-(U8A-IO_L58P_0-PadE20)") (class "Default")
      (node (ref "U8") (pin "E20") (pinfunction "IO_L58P_0_E20") (pintype "passive"))
    )
    (net (code "144") (name "unconnected-(U8A-IO_L59N_0-PadH17)") (class "Default")
      (node (ref "U8") (pin "H17") (pinfunction "IO_L59N_0_H17") (pintype "passive"))
    )
    (net (code "145") (name "unconnected-(U8A-IO_L59P_0-PadJ17)") (class "Default")
      (node (ref "U8") (pin "J17") (pinfunction "IO_L59P_0_J17") (pintype "passive"))
    )
    (net (code "146") (name "unconnected-(U8A-IO_L62N_VREF_0-PadA18)") (class "Default")
      (node (ref "U8") (pin "A18") (pinfunction "IO_L62N_VREF_0_A18") (pintype "passive"))
    )
    (net (code "147") (name "unconnected-(U8A-IO_L62P_0-PadB18)") (class "Default")
      (node (ref "U8") (pin "B18") (pinfunction "IO_L62P_0_B18") (pintype "passive"))
    )
    (net (code "148") (name "unconnected-(U8A-IO_L63N_SCP6_0-PadA19)") (class "Default")
      (node (ref "U8") (pin "A19") (pinfunction "IO_L63N_SCP6_0_A19") (pintype "passive"))
    )
    (net (code "149") (name "unconnected-(U8A-IO_L63P_SCP7_0-PadC19)") (class "Default")
      (node (ref "U8") (pin "C19") (pinfunction "IO_L63P_SCP7_0_C19") (pintype "passive"))
    )
    (net (code "150") (name "unconnected-(U8A-IO_L64N_SCP4_0-PadA20)") (class "Default")
      (node (ref "U8") (pin "A20") (pinfunction "IO_L64N_SCP4_0_A20") (pintype "passive"))
    )
    (net (code "151") (name "unconnected-(U8A-IO_L64P_SCP5_0-PadB20)") (class "Default")
      (node (ref "U8") (pin "B20") (pinfunction "IO_L64P_SCP5_0_B20") (pintype "passive"))
    )
    (net (code "152") (name "unconnected-(U8A-IO_L65N_SCP2_0-PadA21)") (class "Default")
      (node (ref "U8") (pin "A21") (pinfunction "IO_L65N_SCP2_0_A21") (pintype "passive"))
    )
    (net (code "153") (name "unconnected-(U8A-IO_L65P_SCP3_0-PadC21)") (class "Default")
      (node (ref "U8") (pin "C21") (pinfunction "IO_L65P_SCP3_0_C21") (pintype "passive"))
    )
    (net (code "154") (name "unconnected-(U8A-IO_L66N_SCP0_0-PadA22)") (class "Default")
      (node (ref "U8") (pin "A22") (pinfunction "IO_L66N_SCP0_0_A22") (pintype "passive"))
    )
    (net (code "155") (name "unconnected-(U8A-IO_L66P_SCP1_0-PadB22)") (class "Default")
      (node (ref "U8") (pin "B22") (pinfunction "IO_L66P_SCP1_0_B22") (pintype "passive"))
    )
    (net (code "156") (name "unconnected-(U8D-IO_L1N_VREF_3-PadAD7)") (class "Default")
      (node (ref "U8") (pin "AD7") (pinfunction "IO_L1N_VREF_3_AD7") (pintype "passive"))
    )
    (net (code "157") (name "unconnected-(U8D-IO_L1P_3-PadAC7)") (class "Default")
      (node (ref "U8") (pin "AC7") (pinfunction "IO_L1P_3_AC7") (pintype "passive"))
    )
    (net (code "158") (name "unconnected-(U8D-IO_L2N_3-PadAF2)") (class "Default")
      (node (ref "U8") (pin "AF2") (pinfunction "IO_L2N_3_AF2") (pintype "passive"))
    )
    (net (code "159") (name "unconnected-(U8D-IO_L2P_3-PadAE3)") (class "Default")
      (node (ref "U8") (pin "AE3") (pinfunction "IO_L2P_3_AE3") (pintype "passive"))
    )
    (net (code "160") (name "unconnected-(U8D-IO_L3N_3-PadAD4)") (class "Default")
      (node (ref "U8") (pin "AD4") (pinfunction "IO_L3N_3_AD4") (pintype "passive"))
    )
    (net (code "161") (name "unconnected-(U8D-IO_L3P_3-PadAC4)") (class "Default")
      (node (ref "U8") (pin "AC4") (pinfunction "IO_L3P_3_AC4") (pintype "passive"))
    )
    (net (code "162") (name "unconnected-(U8D-IO_L4N_3-PadAB8)") (class "Default")
      (node (ref "U8") (pin "AB8") (pinfunction "IO_L4N_3_AB8") (pintype "passive"))
    )
    (net (code "163") (name "unconnected-(U8D-IO_L4P_3-PadAA8)") (class "Default")
      (node (ref "U8") (pin "AA8") (pinfunction "IO_L4P_3_AA8") (pintype "passive"))
    )
    (net (code "164") (name "unconnected-(U8D-IO_L7N_3-PadY6)") (class "Default")
      (node (ref "U8") (pin "Y6") (pinfunction "IO_L7N_3_Y6") (pintype "passive"))
    )
    (net (code "165") (name "unconnected-(U8D-IO_L7P_3-PadAA7)") (class "Default")
      (node (ref "U8") (pin "AA7") (pinfunction "IO_L7P_3_AA7") (pintype "passive"))
    )
    (net (code "166") (name "unconnected-(U8D-IO_L8N_3-PadAB6)") (class "Default")
      (node (ref "U8") (pin "AB6") (pinfunction "IO_L8N_3_AB6") (pintype "passive"))
    )
    (net (code "167") (name "unconnected-(U8D-IO_L8P_3-PadAB7)") (class "Default")
      (node (ref "U8") (pin "AB7") (pinfunction "IO_L8P_3_AB7") (pintype "passive"))
    )
    (net (code "168") (name "unconnected-(U8D-IO_L9N_3-PadY8)") (class "Default")
      (node (ref "U8") (pin "Y8") (pinfunction "IO_L9N_3_Y8") (pintype "passive"))
    )
    (net (code "169") (name "unconnected-(U8D-IO_L9P_3-PadY9)") (class "Default")
      (node (ref "U8") (pin "Y9") (pinfunction "IO_L9P_3_Y9") (pintype "passive"))
    )
    (net (code "170") (name "unconnected-(U8D-IO_L10N_3-PadAD5)") (class "Default")
      (node (ref "U8") (pin "AD5") (pinfunction "IO_L10N_3_AD5") (pintype "passive"))
    )
    (net (code "171") (name "unconnected-(U8D-IO_L10P_3-PadAC5)") (class "Default")
      (node (ref "U8") (pin "AC5") (pinfunction "IO_L10P_3_AC5") (pintype "passive"))
    )
    (net (code "172") (name "unconnected-(U8D-IO_L15N_3-PadW7)") (class "Default")
      (node (ref "U8") (pin "W7") (pinfunction "IO_L15N_3_W7") (pintype "passive"))
    )
    (net (code "173") (name "unconnected-(U8D-IO_L15P_3-PadW8)") (class "Default")
      (node (ref "U8") (pin "W8") (pinfunction "IO_L15P_3_W8") (pintype "passive"))
    )
    (net (code "174") (name "unconnected-(U8D-IO_L16N_3-PadAB5)") (class "Default")
      (node (ref "U8") (pin "AB5") (pinfunction "IO_L16N_3_AB5") (pintype "passive"))
    )
    (net (code "175") (name "unconnected-(U8D-IO_L16P_3-PadAA5)") (class "Default")
      (node (ref "U8") (pin "AA5") (pinfunction "IO_L16P_3_AA5") (pintype "passive"))
    )
    (net (code "176") (name "unconnected-(U8D-IO_L17N_VREF_3-PadV6)") (class "Default")
      (node (ref "U8") (pin "V6") (pinfunction "IO_L17N_VREF_3_V6") (pintype "passive"))
    )
    (net (code "177") (name "unconnected-(U8D-IO_L17P_3-PadV7)") (class "Default")
      (node (ref "U8") (pin "V7") (pinfunction "IO_L17P_3_V7") (pintype "passive"))
    )
    (net (code "178") (name "unconnected-(U8D-IO_L18N_3-PadAC3)") (class "Default")
      (node (ref "U8") (pin "AC3") (pinfunction "IO_L18N_3_AC3") (pintype "passive"))
    )
    (net (code "179") (name "unconnected-(U8D-IO_L18P_3-PadAB4)") (class "Default")
      (node (ref "U8") (pin "AB4") (pinfunction "IO_L18P_3_AB4") (pintype "passive"))
    )
    (net (code "180") (name "unconnected-(U8D-IO_L19N_3-PadV8)") (class "Default")
      (node (ref "U8") (pin "V8") (pinfunction "IO_L19N_3_V8") (pintype "passive"))
    )
    (net (code "181") (name "unconnected-(U8D-IO_L19P_3-PadW9)") (class "Default")
      (node (ref "U8") (pin "W9") (pinfunction "IO_L19P_3_W9") (pintype "passive"))
    )
    (net (code "182") (name "unconnected-(U8D-IO_L20N_3-PadAA3)") (class "Default")
      (node (ref "U8") (pin "AA3") (pinfunction "IO_L20N_3_AA3") (pintype "passive"))
    )
    (net (code "183") (name "unconnected-(U8D-IO_L20P_3-PadAA4)") (class "Default")
      (node (ref "U8") (pin "AA4") (pinfunction "IO_L20P_3_AA4") (pintype "passive"))
    )
    (net (code "184") (name "unconnected-(U8D-IO_L21N_3-PadV10)") (class "Default")
      (node (ref "U8") (pin "V10") (pinfunction "IO_L21N_3_V10") (pintype "passive"))
    )
    (net (code "185") (name "unconnected-(U8D-IO_L21P_3-PadW10)") (class "Default")
      (node (ref "U8") (pin "W10") (pinfunction "IO_L21P_3_W10") (pintype "passive"))
    )
    (net (code "186") (name "unconnected-(U8D-IO_L22N_3-PadY5)") (class "Default")
      (node (ref "U8") (pin "Y5") (pinfunction "IO_L22N_3_Y5") (pintype "passive"))
    )
    (net (code "187") (name "unconnected-(U8D-IO_L22P_3-PadW5)") (class "Default")
      (node (ref "U8") (pin "W5") (pinfunction "IO_L22P_3_W5") (pintype "passive"))
    )
    (net (code "188") (name "unconnected-(U8D-IO_L23N_3-PadU7)") (class "Default")
      (node (ref "U8") (pin "U7") (pinfunction "IO_L23N_3_U7") (pintype "passive"))
    )
    (net (code "189") (name "unconnected-(U8D-IO_L23P_3-PadU8)") (class "Default")
      (node (ref "U8") (pin "U8") (pinfunction "IO_L23P_3_U8") (pintype "passive"))
    )
    (net (code "190") (name "unconnected-(U8D-IO_L24N_3-PadV5)") (class "Default")
      (node (ref "U8") (pin "V5") (pinfunction "IO_L24N_3_V5") (pintype "passive"))
    )
    (net (code "191") (name "unconnected-(U8D-IO_L24P_3-PadU5)") (class "Default")
      (node (ref "U8") (pin "U5") (pinfunction "IO_L24P_3_U5") (pintype "passive"))
    )
    (net (code "192") (name "unconnected-(U8D-IO_L25N_3-PadU9)") (class "Default")
      (node (ref "U8") (pin "U9") (pinfunction "IO_L25N_3_U9") (pintype "passive"))
    )
    (net (code "193") (name "unconnected-(U8D-IO_L25P_3-PadT10)") (class "Default")
      (node (ref "U8") (pin "T10") (pinfunction "IO_L25P_3_T10") (pintype "passive"))
    )
    (net (code "194") (name "unconnected-(U8D-IO_L27N_3-PadT9)") (class "Default")
      (node (ref "U8") (pin "T9") (pinfunction "IO_L27N_3_T9") (pintype "passive"))
    )
    (net (code "195") (name "unconnected-(U8D-IO_L27P_3-PadR10)") (class "Default")
      (node (ref "U8") (pin "R10") (pinfunction "IO_L27P_3_R10") (pintype "passive"))
    )
    (net (code "196") (name "unconnected-(U8D-IO_L28N_3-PadU3)") (class "Default")
      (node (ref "U8") (pin "U3") (pinfunction "IO_L28N_3_U3") (pintype "passive"))
    )
    (net (code "197") (name "unconnected-(U8D-IO_L28P_3-PadU4)") (class "Default")
      (node (ref "U8") (pin "U4") (pinfunction "IO_L28P_3_U4") (pintype "passive"))
    )
    (net (code "198") (name "unconnected-(U8D-IO_L29N_3-PadT6)") (class "Default")
      (node (ref "U8") (pin "T6") (pinfunction "IO_L29N_3_T6") (pintype "passive"))
    )
    (net (code "199") (name "unconnected-(U8D-IO_L29P_3-PadT8)") (class "Default")
      (node (ref "U8") (pin "T8") (pinfunction "IO_L29P_3_T8") (pintype "passive"))
    )
    (net (code "200") (name "unconnected-(U8D-IO_L30N_3-PadT4)") (class "Default")
      (node (ref "U8") (pin "T4") (pinfunction "IO_L30N_3_T4") (pintype "passive"))
    )
    (net (code "201") (name "unconnected-(U8D-IO_L30P_3-PadR5)") (class "Default")
      (node (ref "U8") (pin "R5") (pinfunction "IO_L30P_3_R5") (pintype "passive"))
    )
    (net (code "202") (name "unconnected-(U8D-IO_L31N_VREF_3-PadR6)") (class "Default")
      (node (ref "U8") (pin "R6") (pinfunction "IO_L31N_VREF_3_R6") (pintype "passive"))
    )
    (net (code "203") (name "unconnected-(U8D-IO_L31P_3-PadR7)") (class "Default")
      (node (ref "U8") (pin "R7") (pinfunction "IO_L31P_3_R7") (pintype "passive"))
    )
    (net (code "204") (name "unconnected-(U8D-IO_L55N_M3A14_3-PadM4)") (class "Default")
      (node (ref "U8") (pin "M4") (pinfunction "IO_L55N_M3A14_3_M4") (pintype "passive"))
    )
    (net (code "205") (name "unconnected-(U8D-IO_L57N_VREF_3-PadL6)") (class "Default")
      (node (ref "U8") (pin "L6") (pinfunction "IO_L57N_VREF_3_L6") (pintype "passive"))
    )
    (net (code "206") (name "unconnected-(U8D-IO_L57P_3-PadL7)") (class "Default")
      (node (ref "U8") (pin "L7") (pinfunction "IO_L57P_3_L7") (pintype "passive"))
    )
    (net (code "207") (name "unconnected-(U8J-NC-PadE12)") (class "Default")
      (node (ref "U8") (pin "E12") (pinfunction "NC_E12") (pintype "passive+no_connect"))
    )
    (net (code "208") (name "unconnected-(U8J-NC-PadF8)") (class "Default")
      (node (ref "U8") (pin "F8") (pinfunction "NC_F8") (pintype "passive+no_connect"))
    )
    (net (code "209") (name "unconnected-(U8J-NC-PadF12)") (class "Default")
      (node (ref "U8") (pin "F12") (pinfunction "NC_F12") (pintype "passive+no_connect"))
    )
    (net (code "210") (name "unconnected-(U8J-NC-PadF14)") (class "Default")
      (node (ref "U8") (pin "F14") (pinfunction "NC_F14") (pintype "passive+no_connect"))
    )
    (net (code "211") (name "unconnected-(U8J-NC-PadG9)") (class "Default")
      (node (ref "U8") (pin "G9") (pinfunction "NC_G9") (pintype "passive+no_connect"))
    )
    (net (code "212") (name "unconnected-(U8J-NC-PadG11)") (class "Default")
      (node (ref "U8") (pin "G11") (pinfunction "NC_G11") (pintype "passive+no_connect"))
    )
    (net (code "213") (name "unconnected-(U8J-NC-PadG13)") (class "Default")
      (node (ref "U8") (pin "G13") (pinfunction "NC_G13") (pintype "passive+no_connect"))
    )
    (net (code "214") (name "unconnected-(U8J-NC-PadH9)") (class "Default")
      (node (ref "U8") (pin "H9") (pinfunction "NC_H9") (pintype "passive+no_connect"))
    )
    (net (code "215") (name "unconnected-(U8J-NC-PadH10)") (class "Default")
      (node (ref "U8") (pin "H10") (pinfunction "NC_H10") (pintype "passive+no_connect"))
    )
    (net (code "216") (name "unconnected-(U8J-NC-PadH12)") (class "Default")
      (node (ref "U8") (pin "H12") (pinfunction "NC_H12") (pintype "passive+no_connect"))
    )
    (net (code "217") (name "unconnected-(U8J-NC-PadH13)") (class "Default")
      (node (ref "U8") (pin "H13") (pinfunction "NC_H13") (pintype "passive+no_connect"))
    )
    (net (code "218") (name "unconnected-(U8J-NC-PadJ11)") (class "Default")
      (node (ref "U8") (pin "J11") (pinfunction "NC_J11") (pintype "passive+no_connect"))
    )
    (net (code "219") (name "unconnected-(U8J-NC-PadJ12)") (class "Default")
      (node (ref "U8") (pin "J12") (pinfunction "NC_J12") (pintype "passive+no_connect"))
    )
    (net (code "220") (name "unconnected-(U8J-NC-PadJ13)") (class "Default")
      (node (ref "U8") (pin "J13") (pinfunction "NC_J13") (pintype "passive+no_connect"))
    )
    (net (code "221") (name "unconnected-(U8J-NC-PadJ16)") (class "Default")
      (node (ref "U8") (pin "J16") (pinfunction "NC_J16") (pintype "passive+no_connect"))
    )
    (net (code "222") (name "unconnected-(U8J-NC-PadK12)") (class "Default")
      (node (ref "U8") (pin "K12") (pinfunction "NC_K12") (pintype "passive+no_connect"))
    )
    (net (code "223") (name "unconnected-(U8J-NC-PadK14)") (class "Default")
      (node (ref "U8") (pin "K14") (pinfunction "NC_K14") (pintype "passive+no_connect"))
    )
    (net (code "224") (name "unconnected-(U8J-NC-PadK15)") (class "Default")
      (node (ref "U8") (pin "K15") (pinfunction "NC_K15") (pintype "passive+no_connect"))
    )
  )
)
